# MCU.net
KiCad netlist of a schematic drawn in Altium Designer
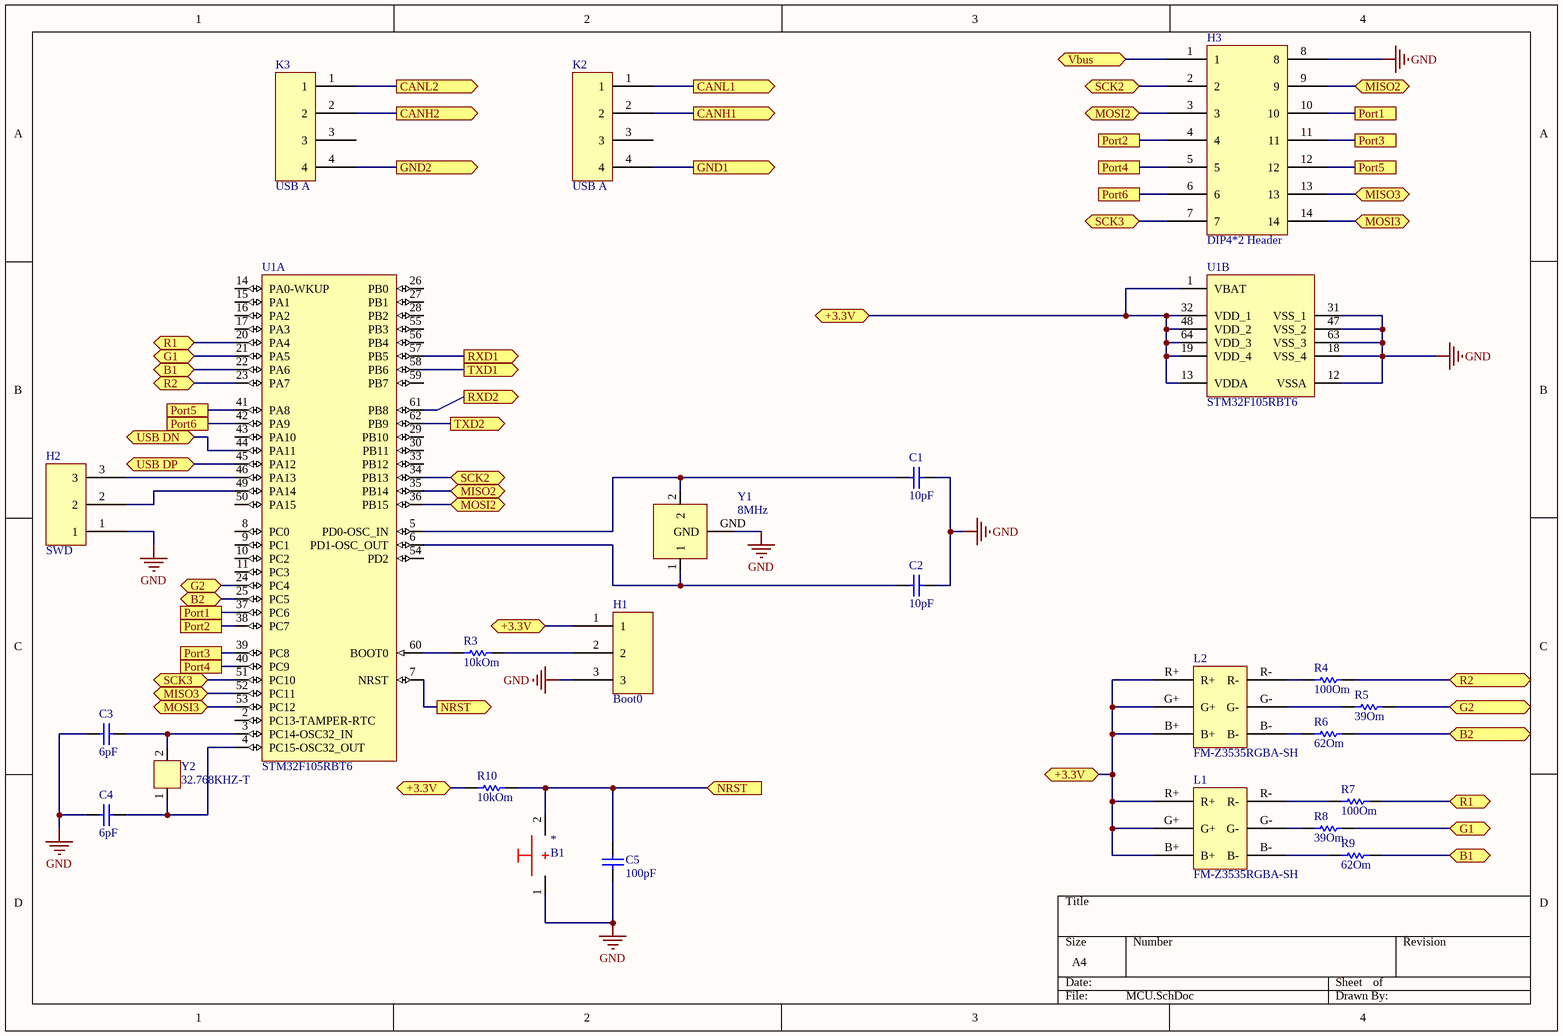
[diagram p0: MCU.SchDoc]

(export (version "E")
  (design (tool "Eeschema 10.0.6"))
  (components
    (comp (ref "*") (value "B1") (footprint "Button 3.5x6x4.3mm") (libsource (lib "lib") (part "Button")))
    (comp (ref "C1")
      (value "10pF")
      (footprint "CAPC1608X90X35ML10T15")
      (fields (field (name "MANUFACTURER") "Murata") (field (name "PART NUMBER") "GCM1885C2A101JA16D"))
      (libsource (lib "Altium Content Vault") (part "CAP"))
    )
    (comp (ref "C2")
      (value "10pF")
      (footprint "CAPC1608X90X35ML10T15")
      (fields (field (name "MANUFACTURER") "Murata") (field (name "PART NUMBER") "GCM1885C2A101JA16D"))
      (libsource (lib "Altium Content Vault") (part "CAP"))
    )
    (comp (ref "C3")
      (value "6pF")
      (footprint "CAPC1608X90X35ML10T15")
      (fields (field (name "MANUFACTURER") "Murata") (field (name "PART NUMBER") "GCM1885C2A101JA16D"))
      (libsource (lib "Altium Content Vault") (part "CAP"))
    )
    (comp (ref "C4")
      (value "6pF")
      (footprint "CAPC1608X90X35ML10T15")
      (fields (field (name "MANUFACTURER") "Murata") (field (name "PART NUMBER") "GCM1885C2A101JA16D"))
      (libsource (lib "Altium Content Vault") (part "CAP"))
    )
    (comp (ref "C5")
      (value "100pF")
      (footprint "CAPC1608X90X35ML10T15")
      (fields (field (name "MANUFACTURER") "Murata") (field (name "PART NUMBER") "GCM1885C2A101JA16D"))
      (libsource (lib "Altium Content Vault") (part "CAP"))
    )
    (comp (ref "H1") (value "Boot0") (footprint "DIP3") (libsource (lib "lib") (part "DIP3 header")))
    (comp (ref "H2") (value "SWD") (footprint "DIP3") (libsource (lib "") (part "DIP3 header_1")))
    (comp (ref "H3")
      (value "DIP4*2 Header")
      (footprint "DIP7*2")
      (libsource (lib "lib") (part "DIP4*2 Header"))
    )
    (comp (ref "K2") (value "USB A") (footprint "USB A") (libsource (lib "lib") (part "USB A")))
    (comp (ref "K3") (value "USB A") (footprint "USB A") (libsource (lib "lib") (part "USB A")))
    (comp (ref "L1")
      (value "FM-Z3535RGBA-SH")
      (footprint "Z3535RGBA")
      (libsource (lib "lib") (part "FM-Z3535RGBA-SH"))
    )
    (comp (ref "L2")
      (value "FM-Z3535RGBA-SH")
      (footprint "Z3535RGBA")
      (libsource (lib "lib") (part "FM-Z3535RGBA-SH"))
    )
    (comp (ref "R3")
      (value "10kOm")
      (footprint "RESC1608X55X30ML20T10")
      (fields (field (name "PART NUMBER") "RK73H1JTTD5101F") (field (name "MANUFACTURER") "KOA Speer"))
      (libsource (lib "Altium Content Vault") (part "RES"))
    )
    (comp (ref "R4")
      (value "100Om")
      (footprint "RESC1608X55X30ML20T10")
      (fields (field (name "PART NUMBER") "RK73H1JTTD5101F") (field (name "MANUFACTURER") "KOA Speer"))
      (libsource (lib "Altium Content Vault") (part "RES"))
    )
    (comp (ref "R5")
      (value "39Om")
      (footprint "RESC1608X55X30ML20T10")
      (fields (field (name "PART NUMBER") "RK73H1JTTD5101F") (field (name "MANUFACTURER") "KOA Speer"))
      (libsource (lib "Altium Content Vault") (part "RES"))
    )
    (comp (ref "R6")
      (value "62Om")
      (footprint "RESC1608X55X30ML20T10")
      (fields (field (name "PART NUMBER") "RK73H1JTTD5101F") (field (name "MANUFACTURER") "KOA Speer"))
      (libsource (lib "Altium Content Vault") (part "RES"))
    )
    (comp (ref "R7")
      (value "100Om")
      (footprint "RESC1608X55X30ML20T10")
      (fields (field (name "PART NUMBER") "RK73H1JTTD5101F") (field (name "MANUFACTURER") "KOA Speer"))
      (libsource (lib "Altium Content Vault") (part "RES"))
    )
    (comp (ref "R8")
      (value "39Om")
      (footprint "RESC1608X55X30ML20T10")
      (fields (field (name "PART NUMBER") "RK73H1JTTD5101F") (field (name "MANUFACTURER") "KOA Speer"))
      (libsource (lib "Altium Content Vault") (part "RES"))
    )
    (comp (ref "R9")
      (value "62Om")
      (footprint "RESC1608X55X30ML20T10")
      (fields (field (name "PART NUMBER") "RK73H1JTTD5101F") (field (name "MANUFACTURER") "KOA Speer"))
      (libsource (lib "Altium Content Vault") (part "RES"))
    )
    (comp (ref "R10")
      (value "10kOm")
      (footprint "RESC1608X55X30ML20T10")
      (fields (field (name "PART NUMBER") "RK73H1JTTD5101F") (field (name "MANUFACTURER") "KOA Speer"))
      (libsource (lib "Altium Content Vault") (part "RES"))
    )
    (comp (ref "U1")
      (value "STM32F105RBT6")
      (footprint "STM-LQFP64_V")
      (libsource (lib "Altium Content Vault") (part "MC-ARM-STM32F10X-SQ64"))
    )
    (comp (ref "Y1")
      (value "8MHz")
      (footprint "SMD-5032 resonator")
      (libsource (lib "lib") (part "TXC Corp 7B08070003 resonator"))
    )
    (comp (ref "Y2")
      (value "32.768KHZ-T")
      (footprint "SMD-2012")
      (libsource (lib "lib") (part "Abracon LLC ABS06-107-32.768KHZ-T"))
    )
  )
  (nets
    (net (code "1") (name "/+3.3V") (class "Default")
      (node (ref "H1") (pin "1") (pinfunction "1_1") (pintype "passive"))
      (node (ref "L1") (pin "B+") (pinfunction "B+_B+") (pintype "passive"))
      (node (ref "L1") (pin "G+") (pinfunction "G+_G+") (pintype "passive"))
      (node (ref "L1") (pin "R+") (pinfunction "R+_R+") (pintype "passive"))
      (node (ref "L2") (pin "B+") (pinfunction "B+_B+") (pintype "passive"))
      (node (ref "L2") (pin "G+") (pinfunction "G+_G+") (pintype "passive"))
      (node (ref "L2") (pin "R+") (pinfunction "R+_R+") (pintype "passive"))
      (node (ref "R10") (pin "1") (pinfunction "1_1") (pintype "passive"))
      (node (ref "U1") (pin "1") (pinfunction "VBAT_1") (pintype "power_in"))
      (node (ref "U1") (pin "13") (pinfunction "VDDA_13") (pintype "power_in"))
      (node (ref "U1") (pin "19") (pinfunction "VDD_4_19") (pintype "power_in"))
      (node (ref "U1") (pin "32") (pinfunction "VDD_1_32") (pintype "power_in"))
      (node (ref "U1") (pin "48") (pinfunction "VDD_2_48") (pintype "power_in"))
      (node (ref "U1") (pin "64") (pinfunction "VDD_3_64") (pintype "power_in"))
    )
    (net (code "2") (name "/B1") (class "Default")
      (node (ref "R9") (pin "2") (pinfunction "2_2") (pintype "passive"))
      (node (ref "U1") (pin "22") (pinfunction "PA6_22") (pintype "bidirectional"))
    )
    (net (code "3") (name "/B2") (class "Default")
      (node (ref "R6") (pin "2") (pinfunction "2_2") (pintype "passive"))
      (node (ref "U1") (pin "25") (pinfunction "PC5_25") (pintype "bidirectional"))
    )
    (net (code "4") (name "/CANH1") (class "Default")
      (node (ref "K2") (pin "2") (pinfunction "2_2") (pintype "passive"))
    )
    (net (code "5") (name "/CANH2") (class "Default")
      (node (ref "K3") (pin "2") (pinfunction "2_2") (pintype "passive"))
    )
    (net (code "6") (name "/CANL1") (class "Default")
      (node (ref "K2") (pin "1") (pinfunction "1_1") (pintype "passive"))
    )
    (net (code "7") (name "/CANL2") (class "Default")
      (node (ref "K3") (pin "1") (pinfunction "1_1") (pintype "passive"))
    )
    (net (code "8") (name "/G1") (class "Default")
      (node (ref "R8") (pin "2") (pinfunction "2_2") (pintype "passive"))
      (node (ref "U1") (pin "21") (pinfunction "PA5_21") (pintype "bidirectional"))
    )
    (net (code "9") (name "/G2") (class "Default")
      (node (ref "R5") (pin "2") (pinfunction "2_2") (pintype "passive"))
      (node (ref "U1") (pin "24") (pinfunction "PC4_24") (pintype "bidirectional"))
    )
    (net (code "10") (name "/GND1") (class "Default")
      (node (ref "K2") (pin "4") (pinfunction "4_4") (pintype "passive"))
    )
    (net (code "11") (name "/GND2") (class "Default")
      (node (ref "K3") (pin "4") (pinfunction "4_4") (pintype "passive"))
    )
    (net (code "12") (name "/MISO2") (class "Default")
      (node (ref "H3") (pin "9") (pinfunction "9_9") (pintype "passive"))
      (node (ref "U1") (pin "35") (pinfunction "PB14_35") (pintype "bidirectional"))
    )
    (net (code "13") (name "/MISO3") (class "Default")
      (node (ref "H3") (pin "13") (pinfunction "13_13") (pintype "passive"))
      (node (ref "U1") (pin "52") (pinfunction "PC11_52") (pintype "bidirectional"))
    )
    (net (code "14") (name "/MOSI2") (class "Default")
      (node (ref "H3") (pin "3") (pinfunction "3_3") (pintype "passive"))
      (node (ref "U1") (pin "36") (pinfunction "PB15_36") (pintype "bidirectional"))
    )
    (net (code "15") (name "/MOSI3") (class "Default")
      (node (ref "H3") (pin "14") (pinfunction "14_14") (pintype "passive"))
      (node (ref "U1") (pin "53") (pinfunction "PC12_53") (pintype "bidirectional"))
    )
    (net (code "16") (name "/NRST") (class "Default")
      (node (ref "*") (pin "2") (pintype "passive"))
      (node (ref "C5") (pin "2") (pinfunction "2_2") (pintype "passive"))
      (node (ref "R10") (pin "2") (pinfunction "2_2") (pintype "passive"))
      (node (ref "U1") (pin "7") (pinfunction "NRST_7") (pintype "bidirectional"))
    )
    (net (code "17") (name "/Port1") (class "Default")
      (node (ref "H3") (pin "10") (pinfunction "10_10") (pintype "passive"))
      (node (ref "U1") (pin "37") (pinfunction "PC6_37") (pintype "bidirectional"))
    )
    (net (code "18") (name "/Port2") (class "Default")
      (node (ref "H3") (pin "4") (pinfunction "4_4") (pintype "passive"))
      (node (ref "U1") (pin "38") (pinfunction "PC7_38") (pintype "bidirectional"))
    )
    (net (code "19") (name "/Port3") (class "Default")
      (node (ref "H3") (pin "11") (pinfunction "11_11") (pintype "passive"))
      (node (ref "U1") (pin "39") (pinfunction "PC8_39") (pintype "bidirectional"))
    )
    (net (code "20") (name "/Port4") (class "Default")
      (node (ref "H3") (pin "5") (pinfunction "5_5") (pintype "passive"))
      (node (ref "U1") (pin "40") (pinfunction "PC9_40") (pintype "bidirectional"))
    )
    (net (code "21") (name "/Port5") (class "Default")
      (node (ref "H3") (pin "12") (pinfunction "12_12") (pintype "passive"))
      (node (ref "U1") (pin "41") (pinfunction "PA8_41") (pintype "bidirectional"))
    )
    (net (code "22") (name "/Port6") (class "Default")
      (node (ref "H3") (pin "6") (pinfunction "6_6") (pintype "passive"))
      (node (ref "U1") (pin "42") (pinfunction "PA9_42") (pintype "bidirectional"))
    )
    (net (code "23") (name "/R1") (class "Default")
      (node (ref "R7") (pin "2") (pinfunction "2_2") (pintype "passive"))
      (node (ref "U1") (pin "20") (pinfunction "PA4_20") (pintype "bidirectional"))
    )
    (net (code "24") (name "/R2") (class "Default")
      (node (ref "R4") (pin "2") (pinfunction "2_2") (pintype "passive"))
      (node (ref "U1") (pin "23") (pinfunction "PA7_23") (pintype "bidirectional"))
    )
    (net (code "25") (name "/RXD1") (class "Default")
      (node (ref "U1") (pin "57") (pinfunction "PB5_57") (pintype "bidirectional"))
    )
    (net (code "26") (name "/RXD2") (class "Default")
      (node (ref "U1") (pin "61") (pinfunction "PB8_61") (pintype "bidirectional"))
    )
    (net (code "27") (name "/SCK2") (class "Default")
      (node (ref "H3") (pin "2") (pinfunction "2_2") (pintype "passive"))
      (node (ref "U1") (pin "34") (pinfunction "PB13_34") (pintype "bidirectional"))
    )
    (net (code "28") (name "/SCK3") (class "Default")
      (node (ref "H3") (pin "7") (pinfunction "7_7") (pintype "passive"))
      (node (ref "U1") (pin "51") (pinfunction "PC10_51") (pintype "bidirectional"))
    )
    (net (code "29") (name "/TXD1") (class "Default")
      (node (ref "U1") (pin "58") (pinfunction "PB6_58") (pintype "bidirectional"))
    )
    (net (code "30") (name "/TXD2") (class "Default")
      (node (ref "U1") (pin "62") (pinfunction "PB9_62") (pintype "bidirectional"))
    )
    (net (code "31") (name "/USB DN") (class "Default")
      (node (ref "U1") (pin "44") (pinfunction "PA11_44") (pintype "bidirectional"))
    )
    (net (code "32") (name "/USB DP") (class "Default")
      (node (ref "U1") (pin "45") (pinfunction "PA12_45") (pintype "bidirectional"))
    )
    (net (code "33") (name "/Vbus") (class "Default")
      (node (ref "H3") (pin "1") (pinfunction "1_1") (pintype "passive"))
    )
    (net (code "34") (name "GND") (class "Default")
      (node (ref "*") (pin "1") (pintype "passive"))
      (node (ref "C1") (pin "2") (pinfunction "2_2") (pintype "passive"))
      (node (ref "C2") (pin "2") (pinfunction "2_2") (pintype "passive"))
      (node (ref "C3") (pin "1") (pinfunction "1_1") (pintype "passive"))
      (node (ref "C4") (pin "1") (pinfunction "1_1") (pintype "passive"))
      (node (ref "C5") (pin "1") (pinfunction "1_1") (pintype "passive"))
      (node (ref "H1") (pin "3") (pinfunction "3_3") (pintype "passive"))
      (node (ref "H2") (pin "1") (pinfunction "1_1") (pintype "passive"))
      (node (ref "H3") (pin "8") (pinfunction "8_8") (pintype "passive"))
      (node (ref "U1") (pin "12") (pinfunction "VSSA_12") (pintype "power_in"))
      (node (ref "U1") (pin "18") (pinfunction "VSS_4_18") (pintype "power_in"))
      (node (ref "U1") (pin "31") (pinfunction "VSS_1_31") (pintype "power_in"))
      (node (ref "U1") (pin "47") (pinfunction "VSS_2_47") (pintype "power_in"))
      (node (ref "U1") (pin "63") (pinfunction "VSS_3_63") (pintype "power_in"))
      (node (ref "Y1") (pin "GND") (pinfunction "GND_GND") (pintype "passive"))
    )
    (net (code "35") (name "Net-(H1-Pad2)") (class "Default")
      (node (ref "H1") (pin "2") (pinfunction "2_2") (pintype "passive"))
      (node (ref "R3") (pin "2") (pinfunction "2_2") (pintype "passive"))
    )
    (net (code "36") (name "Net-(L1-PadB-)") (class "Default")
      (node (ref "L1") (pin "B-") (pinfunction "B-_B-") (pintype "passive"))
      (node (ref "R9") (pin "1") (pinfunction "1_1") (pintype "passive"))
    )
    (net (code "37") (name "Net-(L1-PadG-)") (class "Default")
      (node (ref "L1") (pin "G-") (pinfunction "G-_G-") (pintype "passive"))
      (node (ref "R8") (pin "1") (pinfunction "1_1") (pintype "passive"))
    )
    (net (code "38") (name "Net-(L1-PadR-)") (class "Default")
      (node (ref "L1") (pin "R-") (pinfunction "R-_R-") (pintype "passive"))
      (node (ref "R7") (pin "1") (pinfunction "1_1") (pintype "passive"))
    )
    (net (code "39") (name "Net-(L2-PadB-)") (class "Default")
      (node (ref "L2") (pin "B-") (pinfunction "B-_B-") (pintype "passive"))
      (node (ref "R6") (pin "1") (pinfunction "1_1") (pintype "passive"))
    )
    (net (code "40") (name "Net-(L2-PadG-)") (class "Default")
      (node (ref "L2") (pin "G-") (pinfunction "G-_G-") (pintype "passive"))
      (node (ref "R5") (pin "1") (pinfunction "1_1") (pintype "passive"))
    )
    (net (code "41") (name "Net-(L2-PadR-)") (class "Default")
      (node (ref "L2") (pin "R-") (pinfunction "R-_R-") (pintype "passive"))
      (node (ref "R4") (pin "1") (pinfunction "1_1") (pintype "passive"))
    )
    (net (code "42") (name "Net-(U1A-BOOT0)") (class "Default")
      (node (ref "R3") (pin "1") (pinfunction "1_1") (pintype "passive"))
      (node (ref "U1") (pin "60") (pinfunction "BOOT0_60") (pintype "input"))
    )
    (net (code "43") (name "Net-(U1A-PA13)") (class "Default")
      (node (ref "H2") (pin "3") (pinfunction "3_3") (pintype "passive"))
      (node (ref "U1") (pin "46") (pinfunction "PA13_46") (pintype "bidirectional"))
    )
    (net (code "44") (name "Net-(U1A-PA14)") (class "Default")
      (node (ref "H2") (pin "2") (pinfunction "2_2") (pintype "passive"))
      (node (ref "U1") (pin "49") (pinfunction "PA14_49") (pintype "bidirectional"))
    )
    (net (code "45") (name "Net-(U1A-PC14-OSC32_IN)") (class "Default")
      (node (ref "C3") (pin "2") (pinfunction "2_2") (pintype "passive"))
      (node (ref "U1") (pin "3") (pinfunction "PC14-OSC32_IN_3") (pintype "bidirectional"))
      (node (ref "Y2") (pin "2") (pintype "passive"))
    )
    (net (code "46") (name "Net-(U1A-PC15-OSC32_OUT)") (class "Default")
      (node (ref "C4") (pin "2") (pinfunction "2_2") (pintype "passive"))
      (node (ref "U1") (pin "4") (pinfunction "PC15-OSC32_OUT_4") (pintype "bidirectional"))
      (node (ref "Y2") (pin "1") (pintype "passive"))
    )
    (net (code "47") (name "Net-(U1A-PD0-OSC_IN)") (class "Default")
      (node (ref "C1") (pin "1") (pinfunction "1_1") (pintype "passive"))
      (node (ref "U1") (pin "5") (pinfunction "PD0-OSC_IN_5") (pintype "bidirectional"))
      (node (ref "Y1") (pin "2") (pinfunction "2_2") (pintype "passive"))
    )
    (net (code "48") (name "Net-(U1A-PD1-OSC_OUT)") (class "Default")
      (node (ref "C2") (pin "1") (pinfunction "1_1") (pintype "passive"))
      (node (ref "U1") (pin "6") (pinfunction "PD1-OSC_OUT_6") (pintype "bidirectional"))
      (node (ref "Y1") (pin "1") (pinfunction "1_1") (pintype "passive"))
    )
    (net (code "49") (name "unconnected-(K2-Pad3)") (class "Default")
      (node (ref "K2") (pin "3") (pinfunction "3_3") (pintype "passive"))
    )
    (net (code "50") (name "unconnected-(K3-Pad3)") (class "Default")
      (node (ref "K3") (pin "3") (pinfunction "3_3") (pintype "passive"))
    )
    (net (code "51") (name "unconnected-(U1A-PA0-WKUP-Pad14)") (class "Default")
      (node (ref "U1") (pin "14") (pinfunction "PA0-WKUP_14") (pintype "bidirectional"))
    )
    (net (code "52") (name "unconnected-(U1A-PA1-Pad15)") (class "Default")
      (node (ref "U1") (pin "15") (pinfunction "PA1_15") (pintype "bidirectional"))
    )
    (net (code "53") (name "unconnected-(U1A-PA2-Pad16)") (class "Default")
      (node (ref "U1") (pin "16") (pinfunction "PA2_16") (pintype "bidirectional"))
    )
    (net (code "54") (name "unconnected-(U1A-PA3-Pad17)") (class "Default")
      (node (ref "U1") (pin "17") (pinfunction "PA3_17") (pintype "bidirectional"))
    )
    (net (code "55") (name "unconnected-(U1A-PA10-Pad43)") (class "Default")
      (node (ref "U1") (pin "43") (pinfunction "PA10_43") (pintype "bidirectional"))
    )
    (net (code "56") (name "unconnected-(U1A-PA15-Pad50)") (class "Default")
      (node (ref "U1") (pin "50") (pinfunction "PA15_50") (pintype "bidirectional"))
    )
    (net (code "57") (name "unconnected-(U1A-PB0-Pad26)") (class "Default")
      (node (ref "U1") (pin "26") (pinfunction "PB0_26") (pintype "bidirectional"))
    )
    (net (code "58") (name "unconnected-(U1A-PB1-Pad27)") (class "Default")
      (node (ref "U1") (pin "27") (pinfunction "PB1_27") (pintype "bidirectional"))
    )
    (net (code "59") (name "unconnected-(U1A-PB2-Pad28)") (class "Default")
      (node (ref "U1") (pin "28") (pinfunction "PB2_28") (pintype "bidirectional"))
    )
    (net (code "60") (name "unconnected-(U1A-PB3-Pad55)") (class "Default")
      (node (ref "U1") (pin "55") (pinfunction "PB3_55") (pintype "bidirectional"))
    )
    (net (code "61") (name "unconnected-(U1A-PB4-Pad56)") (class "Default")
      (node (ref "U1") (pin "56") (pinfunction "PB4_56") (pintype "bidirectional"))
    )
    (net (code "62") (name "unconnected-(U1A-PB7-Pad59)") (class "Default")
      (node (ref "U1") (pin "59") (pinfunction "PB7_59") (pintype "bidirectional"))
    )
    (net (code "63") (name "unconnected-(U1A-PB10-Pad29)") (class "Default")
      (node (ref "U1") (pin "29") (pinfunction "PB10_29") (pintype "bidirectional"))
    )
    (net (code "64") (name "unconnected-(U1A-PB11-Pad30)") (class "Default")
      (node (ref "U1") (pin "30") (pinfunction "PB11_30") (pintype "bidirectional"))
    )
    (net (code "65") (name "unconnected-(U1A-PB12-Pad33)") (class "Default")
      (node (ref "U1") (pin "33") (pinfunction "PB12_33") (pintype "bidirectional"))
    )
    (net (code "66") (name "unconnected-(U1A-PC0-Pad8)") (class "Default")
      (node (ref "U1") (pin "8") (pinfunction "PC0_8") (pintype "bidirectional"))
    )
    (net (code "67") (name "unconnected-(U1A-PC1-Pad9)") (class "Default")
      (node (ref "U1") (pin "9") (pinfunction "PC1_9") (pintype "bidirectional"))
    )
    (net (code "68") (name "unconnected-(U1A-PC2-Pad10)") (class "Default")
      (node (ref "U1") (pin "10") (pinfunction "PC2_10") (pintype "bidirectional"))
    )
    (net (code "69") (name "unconnected-(U1A-PC3-Pad11)") (class "Default")
      (node (ref "U1") (pin "11") (pinfunction "PC3_11") (pintype "bidirectional"))
    )
    (net (code "70") (name "unconnected-(U1A-PC13-TAMPER-RTC-Pad2)") (class "Default")
      (node (ref "U1") (pin "2") (pinfunction "PC13-TAMPER-RTC_2") (pintype "bidirectional"))
    )
    (net (code "71") (name "unconnected-(U1A-PD2-Pad54)") (class "Default")
      (node (ref "U1") (pin "54") (pinfunction "PD2_54") (pintype "bidirectional"))
    )
  )
)
